# Ethernet.net
KiCad netlist of a schematic drawn in Altium Designer
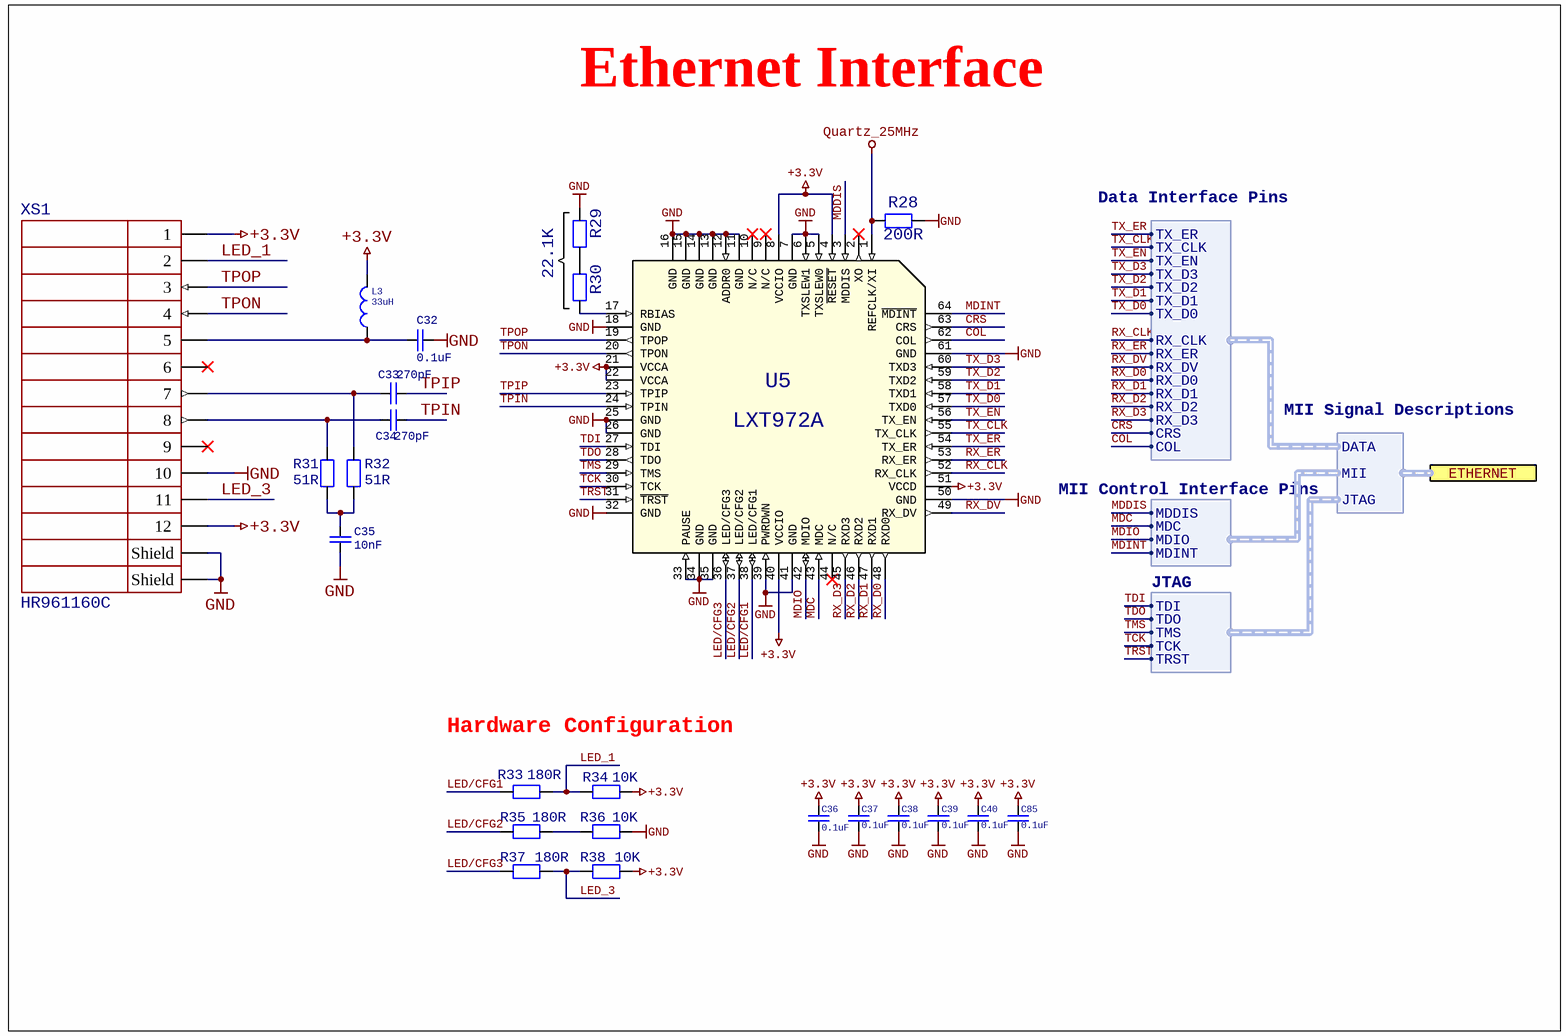
[diagram p0: Ethernet.SchDoc]

(export (version "E")
  (design (tool "Eeschema 10.0.6"))
  (components
    (comp (ref "C32")
      (value "0.1uF")
      (footprint "Passive:C_0603")
      (description "Non-polarised capacitor")
      (libsource (lib "Passive") (part "C"))
    )
    (comp (ref "C33")
      (value "270pF")
      (footprint "Passive:C_0603")
      (description "Non-polarised capacitor")
      (libsource (lib "Passive") (part "C"))
    )
    (comp (ref "C34")
      (value "270pF")
      (footprint "Passive:C_0603")
      (description "Non-polarised capacitor")
      (libsource (lib "Passive") (part "C"))
    )
    (comp (ref "C35")
      (value "10nF")
      (footprint "Passive:C_0603")
      (description "Non-polarised capacitor")
      (libsource (lib "Passive") (part "C"))
    )
    (comp (ref "C36")
      (value "0.1uF")
      (footprint "Passive:C_0603")
      (description "Non-polarised capacitor")
      (libsource (lib "Passive") (part "C"))
    )
    (comp (ref "C37")
      (value "0.1uF")
      (footprint "Passive:C_0603")
      (description "Non-polarised capacitor")
      (libsource (lib "Passive") (part "C"))
    )
    (comp (ref "C38")
      (value "0.1uF")
      (footprint "Passive:C_0603")
      (description "Non-polarised capacitor")
      (libsource (lib "Passive") (part "C"))
    )
    (comp (ref "C39")
      (value "0.1uF")
      (footprint "Passive:C_0603")
      (description "Non-polarised capacitor")
      (libsource (lib "Passive") (part "C"))
    )
    (comp (ref "C40")
      (value "0.1uF")
      (footprint "Passive:C_0603")
      (description "Non-polarised capacitor")
      (libsource (lib "Passive") (part "C"))
    )
    (comp (ref "C85")
      (value "0.1uF")
      (footprint "Passive:C_0603")
      (description "Non-polarised capacitor")
      (libsource (lib "Passive") (part "C"))
    )
    (comp (ref "L3") (value "33uH") (footprint "Passive:L_1206") (libsource (lib "Passive") (part "L_2")))
    (comp (ref "R28") (value "200R") (footprint "Passive:R_0603") (libsource (lib "Passive") (part "R")))
    (comp (ref "R29") (value "?") (footprint "Passive:R_0603") (libsource (lib "") (part "R_2")))
    (comp (ref "R30") (value "22.1K") (footprint "Passive:R_0603") (libsource (lib "") (part "R_1")))
    (comp (ref "R31") (value "51R") (footprint "Passive:R_0603") (libsource (lib "") (part "R_1")))
    (comp (ref "R32") (value "51R") (footprint "Passive:R_0603") (libsource (lib "") (part "R_1")))
    (comp (ref "R33") (value "180R") (footprint "Passive:R_0603") (libsource (lib "Passive") (part "R")))
    (comp (ref "R34") (value "10K") (footprint "Passive:R_0603") (libsource (lib "Passive") (part "R")))
    (comp (ref "R35") (value "180R") (footprint "Passive:R_0603") (libsource (lib "Passive") (part "R")))
    (comp (ref "R36") (value "10K") (footprint "Passive:R_0603") (libsource (lib "Passive") (part "R")))
    (comp (ref "R37") (value "180R") (footprint "Passive:R_0603") (libsource (lib "Passive") (part "R")))
    (comp (ref "R38") (value "10K") (footprint "Passive:R_0603") (libsource (lib "Passive") (part "R")))
    (comp (ref "U5")
      (value "LXT972A")
      (footprint "SMD_LQFP:LQFP-64")
      (description "10/100 Ethernet Transceiver")
      (libsource (lib "Device") (part "LXT972A"))
    )
    (comp (ref "XS1")
      (value "HR961160C")
      (footprint "Connector_Other:HR961160C")
      (libsource (lib "Connector") (part "HR961160C"))
    )
  )
  (nets
    (net (code "9") (name "+3.3V") (class "Default")
      (node (ref "C36") (pin "1") (pinfunction "1_1") (pintype "passive"))
      (node (ref "C37") (pin "1") (pinfunction "1_1") (pintype "passive"))
      (node (ref "C38") (pin "1") (pinfunction "1_1") (pintype "passive"))
      (node (ref "C39") (pin "1") (pinfunction "1_1") (pintype "passive"))
      (node (ref "C40") (pin "1") (pinfunction "1_1") (pintype "passive"))
      (node (ref "C85") (pin "1") (pinfunction "1_1") (pintype "passive"))
      (node (ref "L3") (pin "2") (pinfunction "2_2") (pintype "passive"))
      (node (ref "R34") (pin "2") (pinfunction "2_2") (pintype "passive"))
      (node (ref "R38") (pin "2") (pinfunction "2_2") (pintype "passive"))
      (node (ref "U5") (pin "21") (pinfunction "VCCA_21") (pintype "passive"))
      (node (ref "U5") (pin "22") (pinfunction "VCCA_22") (pintype "passive"))
      (node (ref "U5") (pin "4") (pinfunction "RESET_4") (pintype "input"))
      (node (ref "U5") (pin "40") (pinfunction "VCCIO_40") (pintype "passive"))
      (node (ref "U5") (pin "51") (pinfunction "VCCD_51") (pintype "passive"))
      (node (ref "U5") (pin "8") (pinfunction "VCCIO_8") (pintype "passive"))
      (node (ref "XS1") (pin "1") (pinfunction "1_1") (pintype "passive"))
      (node (ref "XS1") (pin "12") (pinfunction "12_12") (pintype "passive"))
    )
    (net (code "10") (name "/COL") (class "Default")
      (node (ref "U5") (pin "62") (pinfunction "COL_62") (pintype "output"))
    )
    (net (code "11") (name "/CRS") (class "Default")
      (node (ref "U5") (pin "63") (pinfunction "CRS_63") (pintype "output"))
    )
    (net (code "12") (name "/LED_1") (class "Default")
      (node (ref "R33") (pin "2") (pinfunction "2_2") (pintype "passive"))
      (node (ref "R34") (pin "1") (pinfunction "1_1") (pintype "passive"))
      (node (ref "XS1") (pin "2") (pinfunction "2_2") (pintype "passive"))
    )
    (net (code "13") (name "/LED_3") (class "Default")
      (node (ref "R37") (pin "2") (pinfunction "2_2") (pintype "passive"))
      (node (ref "R38") (pin "1") (pinfunction "1_1") (pintype "passive"))
      (node (ref "XS1") (pin "11") (pinfunction "11_11") (pintype "passive"))
    )
    (net (code "14") (name "/LED{slash}CFG1") (class "Default")
      (node (ref "R33") (pin "1") (pinfunction "1_1") (pintype "passive"))
      (node (ref "U5") (pin "38") (pinfunction "LED/CFG1_38") (pintype "bidirectional"))
    )
    (net (code "15") (name "/LED{slash}CFG2") (class "Default")
      (node (ref "R35") (pin "1") (pinfunction "1_1") (pintype "passive"))
      (node (ref "U5") (pin "37") (pinfunction "LED/CFG2_37") (pintype "bidirectional"))
    )
    (net (code "16") (name "/LED{slash}CFG3") (class "Default")
      (node (ref "R37") (pin "1") (pinfunction "1_1") (pintype "passive"))
      (node (ref "U5") (pin "36") (pinfunction "LED/CFG3_36") (pintype "bidirectional"))
    )
    (net (code "17") (name "/MDC") (class "Default")
      (node (ref "U5") (pin "43") (pinfunction "MDC_43") (pintype "input"))
    )
    (net (code "18") (name "/MDDIS") (class "Default")
      (node (ref "U5") (pin "3") (pinfunction "MDDIS_3") (pintype "input"))
    )
    (net (code "19") (name "/MDINT") (class "Default")
      (node (ref "U5") (pin "64") (pinfunction "MDINT_64") (pintype "passive"))
    )
    (net (code "20") (name "/MDIO") (class "Default")
      (node (ref "U5") (pin "42") (pinfunction "MDIO_42") (pintype "bidirectional"))
    )
    (net (code "21") (name "/RX_CLK") (class "Default")
      (node (ref "U5") (pin "52") (pinfunction "RX_CLK_52") (pintype "output"))
    )
    (net (code "22") (name "/RX_D0") (class "Default")
      (node (ref "U5") (pin "48") (pinfunction "RXD0_48") (pintype "output"))
    )
    (net (code "23") (name "/RX_D1") (class "Default")
      (node (ref "U5") (pin "47") (pinfunction "RXD1_47") (pintype "output"))
    )
    (net (code "24") (name "/RX_D2") (class "Default")
      (node (ref "U5") (pin "46") (pinfunction "RXD2_46") (pintype "output"))
    )
    (net (code "25") (name "/RX_D3") (class "Default")
      (node (ref "U5") (pin "45") (pinfunction "RXD3_45") (pintype "output"))
    )
    (net (code "26") (name "/RX_DV") (class "Default")
      (node (ref "U5") (pin "49") (pinfunction "RX_DV_49") (pintype "output"))
    )
    (net (code "27") (name "/RX_ER") (class "Default")
      (node (ref "U5") (pin "53") (pinfunction "RX_ER_53") (pintype "output"))
    )
    (net (code "28") (name "/TCK") (class "Default")
      (node (ref "U5") (pin "30") (pinfunction "TCK_30") (pintype "input"))
    )
    (net (code "29") (name "/TDI") (class "Default")
      (node (ref "U5") (pin "27") (pinfunction "TDI_27") (pintype "input"))
    )
    (net (code "30") (name "/TDO") (class "Default")
      (node (ref "U5") (pin "28") (pinfunction "TDO_28") (pintype "output"))
    )
    (net (code "31") (name "/TMS") (class "Default")
      (node (ref "U5") (pin "29") (pinfunction "TMS_29") (pintype "input"))
    )
    (net (code "32") (name "/TPIN") (class "Default")
      (node (ref "C34") (pin "2") (pinfunction "2_2") (pintype "passive"))
      (node (ref "U5") (pin "24") (pinfunction "TPIN_24") (pintype "input"))
    )
    (net (code "33") (name "/TPIP") (class "Default")
      (node (ref "C33") (pin "2") (pinfunction "2_2") (pintype "passive"))
      (node (ref "U5") (pin "23") (pinfunction "TPIP_23") (pintype "input"))
    )
    (net (code "34") (name "/TPON") (class "Default")
      (node (ref "U5") (pin "20") (pinfunction "TPON_20") (pintype "output"))
      (node (ref "XS1") (pin "4") (pinfunction "4_4") (pintype "input"))
    )
    (net (code "35") (name "/TPOP") (class "Default")
      (node (ref "U5") (pin "19") (pinfunction "TPOP_19") (pintype "output"))
      (node (ref "XS1") (pin "3") (pinfunction "3_3") (pintype "input"))
    )
    (net (code "36") (name "/TRST") (class "Default")
      (node (ref "U5") (pin "31") (pinfunction "TRST_31") (pintype "input"))
    )
    (net (code "37") (name "/TX_CLK") (class "Default")
      (node (ref "U5") (pin "55") (pinfunction "TX_CLK_55") (pintype "output"))
    )
    (net (code "38") (name "/TX_D0") (class "Default")
      (node (ref "U5") (pin "57") (pinfunction "TXD0_57") (pintype "input"))
    )
    (net (code "39") (name "/TX_D1") (class "Default")
      (node (ref "U5") (pin "58") (pinfunction "TXD1_58") (pintype "input"))
    )
    (net (code "40") (name "/TX_D2") (class "Default")
      (node (ref "U5") (pin "59") (pinfunction "TXD2_59") (pintype "input"))
    )
    (net (code "41") (name "/TX_D3") (class "Default")
      (node (ref "U5") (pin "60") (pinfunction "TXD3_60") (pintype "input"))
    )
    (net (code "42") (name "/TX_EN") (class "Default")
      (node (ref "U5") (pin "56") (pinfunction "TX_EN_56") (pintype "input"))
    )
    (net (code "43") (name "/TX_ER") (class "Default")
      (node (ref "U5") (pin "54") (pinfunction "TX_ER_54") (pintype "input"))
    )
    (net (code "48") (name "GND") (class "Default")
      (node (ref "C32") (pin "2") (pinfunction "2_2") (pintype "passive"))
      (node (ref "C35") (pin "2") (pinfunction "2_2") (pintype "passive"))
      (node (ref "C36") (pin "2") (pinfunction "2_2") (pintype "passive"))
      (node (ref "C37") (pin "2") (pinfunction "2_2") (pintype "passive"))
      (node (ref "C38") (pin "2") (pinfunction "2_2") (pintype "passive"))
      (node (ref "C39") (pin "2") (pinfunction "2_2") (pintype "passive"))
      (node (ref "C40") (pin "2") (pinfunction "2_2") (pintype "passive"))
      (node (ref "C85") (pin "2") (pinfunction "2_2") (pintype "passive"))
      (node (ref "R28") (pin "2") (pinfunction "2_2") (pintype "passive"))
      (node (ref "R29") (pin "2") (pinfunction "2_2") (pintype "passive"))
      (node (ref "R36") (pin "2") (pinfunction "2_2") (pintype "passive"))
      (node (ref "U5") (pin "11") (pinfunction "GND_11") (pintype "passive"))
      (node (ref "U5") (pin "12") (pinfunction "ADDR0_12") (pintype "input"))
      (node (ref "U5") (pin "13") (pinfunction "GND_13") (pintype "passive"))
      (node (ref "U5") (pin "14") (pinfunction "GND_14") (pintype "passive"))
      (node (ref "U5") (pin "15") (pinfunction "GND_15") (pintype "passive"))
      (node (ref "U5") (pin "16") (pinfunction "GND_16") (pintype "passive"))
      (node (ref "U5") (pin "18") (pinfunction "GND_18") (pintype "passive"))
      (node (ref "U5") (pin "25") (pinfunction "GND_25") (pintype "passive"))
      (node (ref "U5") (pin "26") (pinfunction "GND_26") (pintype "passive"))
      (node (ref "U5") (pin "32") (pinfunction "GND_32") (pintype "passive"))
      (node (ref "U5") (pin "33") (pinfunction "PAUSE_33") (pintype "input"))
      (node (ref "U5") (pin "34") (pinfunction "GND_34") (pintype "passive"))
      (node (ref "U5") (pin "35") (pinfunction "GND_35") (pintype "passive"))
      (node (ref "U5") (pin "39") (pinfunction "PWRDWN_39") (pintype "input"))
      (node (ref "U5") (pin "41") (pinfunction "GND_41") (pintype "passive"))
      (node (ref "U5") (pin "5") (pinfunction "TXSLEW0_5") (pintype "input"))
      (node (ref "U5") (pin "50") (pinfunction "GND_50") (pintype "passive"))
      (node (ref "U5") (pin "6") (pinfunction "TXSLEW1_6") (pintype "input"))
      (node (ref "U5") (pin "61") (pinfunction "GND_61") (pintype "passive"))
      (node (ref "U5") (pin "7") (pinfunction "GND_7") (pintype "passive"))
      (node (ref "XS1") (pin "10") (pinfunction "10_10") (pintype "passive"))
      (node (ref "XS1") (pin "Shield") (pinfunction "Shield_Shield") (pintype "passive"))
    )
    (net (code "49") (name "Net-(C32-Pad1)") (class "Default")
      (node (ref "C32") (pin "1") (pinfunction "1_1") (pintype "passive"))
      (node (ref "L3") (pin "1") (pinfunction "1_1") (pintype "passive"))
      (node (ref "XS1") (pin "5") (pinfunction "5_5") (pintype "passive"))
    )
    (net (code "50") (name "Net-(C33-Pad1)") (class "Default")
      (node (ref "C33") (pin "1") (pinfunction "1_1") (pintype "passive"))
      (node (ref "R32") (pin "1") (pinfunction "1_1") (pintype "passive"))
      (node (ref "XS1") (pin "7") (pinfunction "7_7") (pintype "output"))
    )
    (net (code "51") (name "Net-(C34-Pad1)") (class "Default")
      (node (ref "C34") (pin "1") (pinfunction "1_1") (pintype "passive"))
      (node (ref "R31") (pin "1") (pinfunction "1_1") (pintype "passive"))
      (node (ref "XS1") (pin "8") (pinfunction "8_8") (pintype "output"))
    )
    (net (code "52") (name "Net-(C35-Pad1)") (class "Default")
      (node (ref "C35") (pin "1") (pinfunction "1_1") (pintype "passive"))
      (node (ref "R31") (pin "2") (pinfunction "2_2") (pintype "passive"))
      (node (ref "R32") (pin "2") (pinfunction "2_2") (pintype "passive"))
    )
    (net (code "53") (name "Net-(R29-Pad1)") (class "Default")
      (node (ref "R29") (pin "1") (pinfunction "1_1") (pintype "passive"))
      (node (ref "R30") (pin "1") (pinfunction "1_1") (pintype "passive"))
    )
    (net (code "54") (name "Net-(R35-Pad2)") (class "Default")
      (node (ref "R35") (pin "2") (pinfunction "2_2") (pintype "passive"))
      (node (ref "R36") (pin "1") (pinfunction "1_1") (pintype "passive"))
    )
    (net (code "55") (name "Net-(U5-RBIAS)") (class "Default")
      (node (ref "R30") (pin "2") (pinfunction "2_2") (pintype "passive"))
      (node (ref "U5") (pin "17") (pinfunction "RBIAS_17") (pintype "input"))
    )
    (net (code "56") (name "Quartz_25MHz") (class "Default")
      (node (ref "R28") (pin "1") (pinfunction "1_1") (pintype "passive"))
      (node (ref "U5") (pin "1") (pinfunction "REFCLK/XI_1") (pintype "input"))
    )
    (net (code "57") (name "unconnected-(U5-N{slash}C-Pad9)") (class "Default")
      (node (ref "U5") (pin "9") (pinfunction "N/C_9") (pintype "passive+no_connect"))
    )
    (net (code "58") (name "unconnected-(U5-N{slash}C-Pad10)") (class "Default")
      (node (ref "U5") (pin "10") (pinfunction "N/C_10") (pintype "passive+no_connect"))
    )
    (net (code "59") (name "unconnected-(U5-N{slash}C-Pad44)") (class "Default")
      (node (ref "U5") (pin "44") (pinfunction "N/C_44") (pintype "passive+no_connect"))
    )
    (net (code "60") (name "unconnected-(U5-XO-Pad2)") (class "Default")
      (node (ref "U5") (pin "2") (pinfunction "XO_2") (pintype "output+no_connect"))
    )
    (net (code "61") (name "unconnected-(XS1-Pad6)") (class "Default")
      (node (ref "XS1") (pin "6") (pinfunction "6_6") (pintype "passive+no_connect"))
    )
    (net (code "62") (name "unconnected-(XS1-Pad9)") (class "Default")
      (node (ref "XS1") (pin "9") (pinfunction "9_9") (pintype "passive+no_connect"))
    )
  )
)
